# Mouse-112.net
KiCad netlist of a schematic drawn in EAGLE
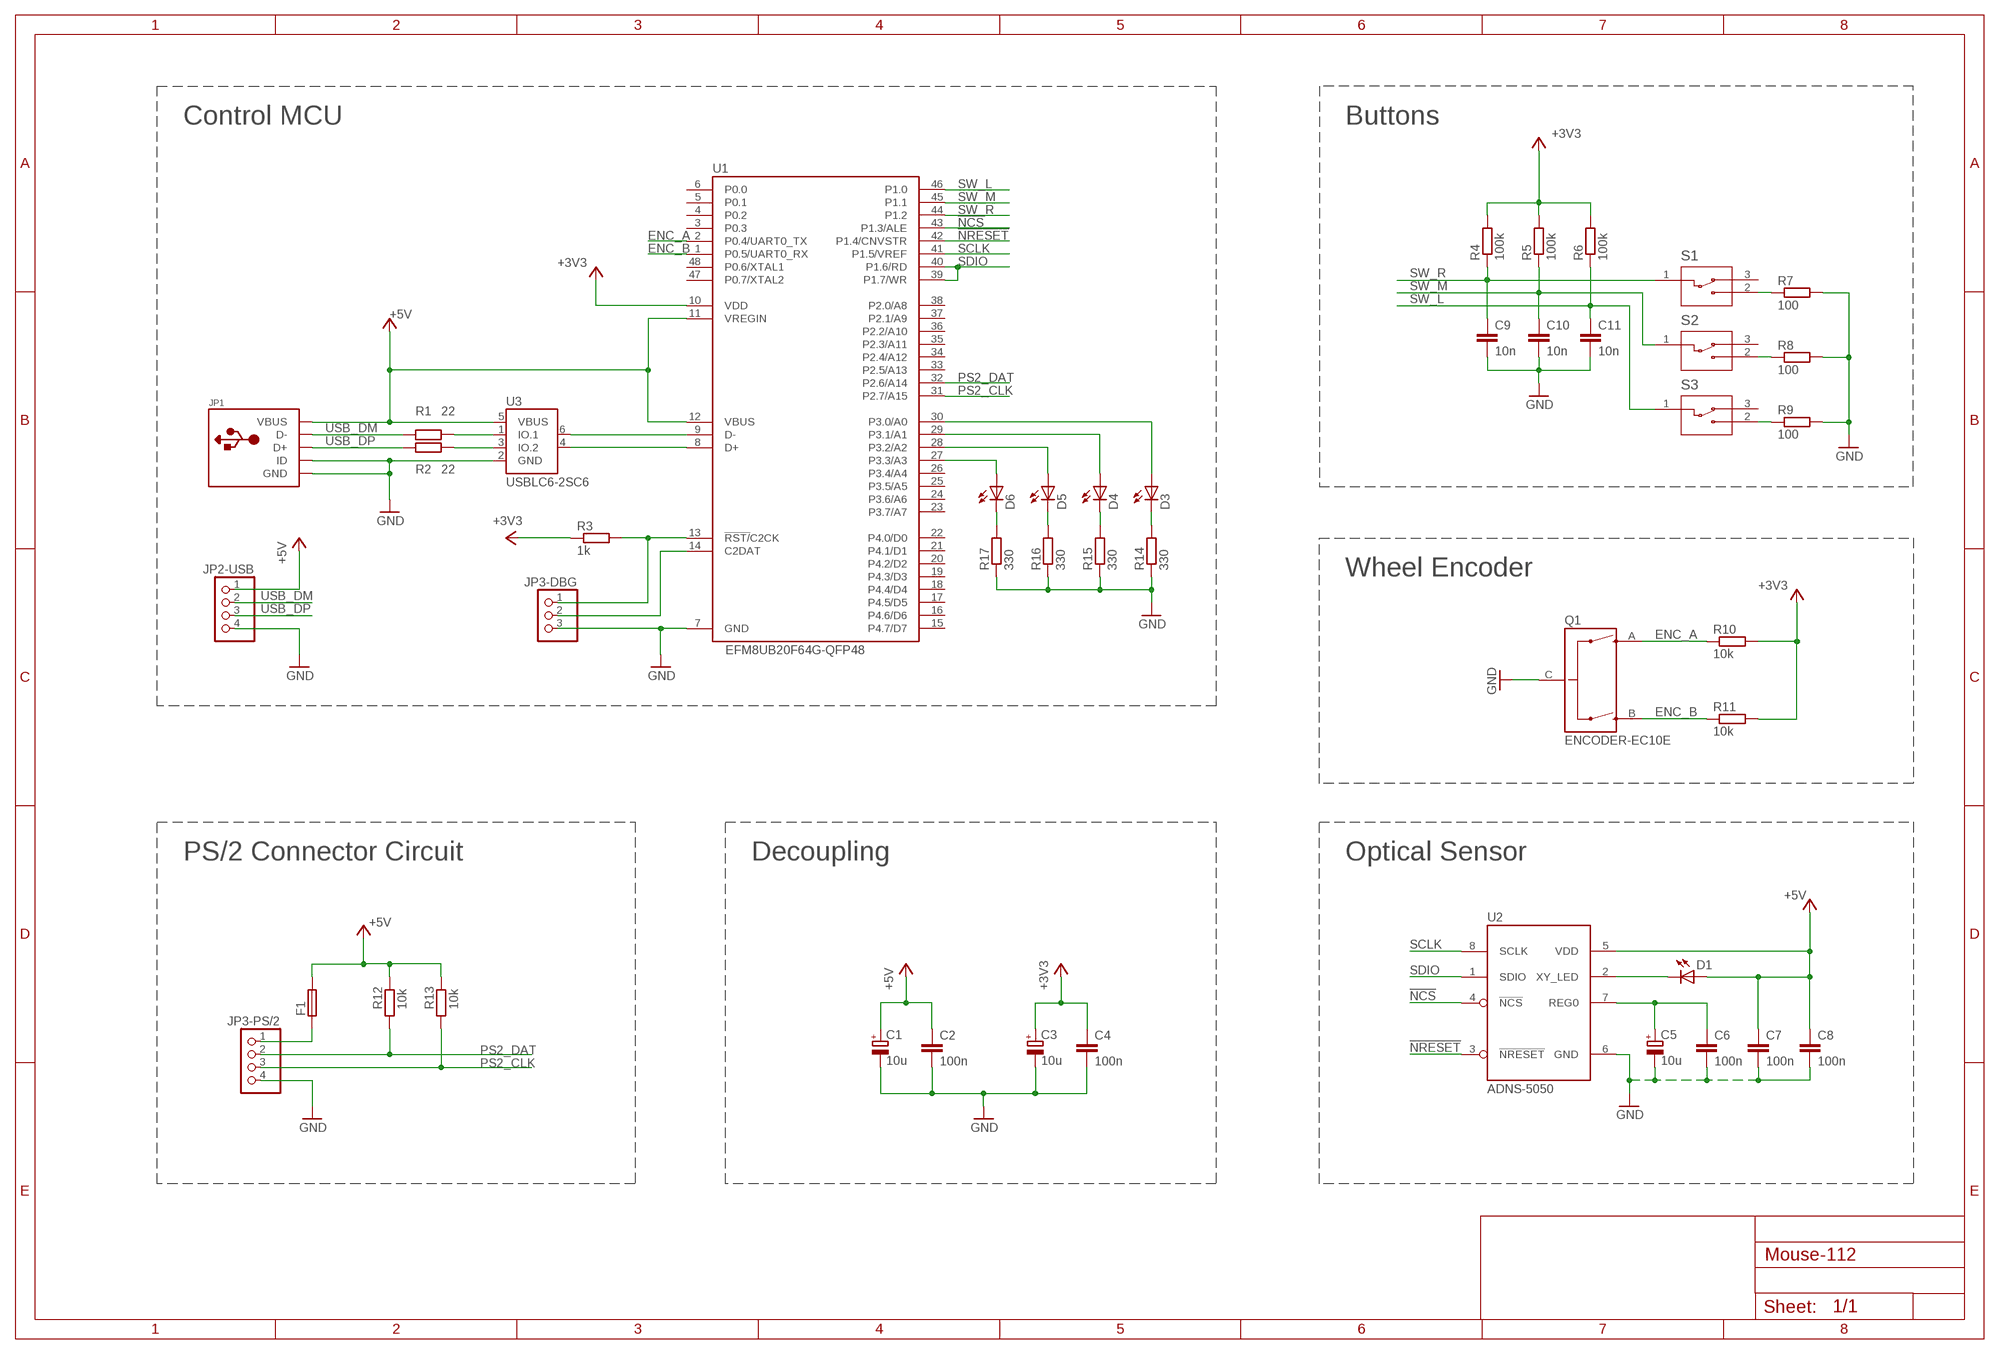
[diagram p0: schematic, sheet 1]

(export (version "E")
  (design (tool "Eeschema 10.0.6"))
  (components
    (comp (ref "C1")
      (value "10u")
      (footprint "eagle-import:RCL-1206F-POL")
      (libsource (lib "eagle-import") (part "CPOL-EU"))
    )
    (comp (ref "C2")
      (value "100n")
      (footprint "eagle-import:RCL-0805F")
      (libsource (lib "eagle-import") (part "C-EU0805"))
    )
    (comp (ref "C3")
      (value "10u")
      (footprint "eagle-import:RCL-1206F-POL")
      (libsource (lib "eagle-import") (part "CPOL-EU"))
    )
    (comp (ref "C4")
      (value "100n")
      (footprint "eagle-import:RCL-0805F")
      (libsource (lib "eagle-import") (part "C-EU0805"))
    )
    (comp (ref "C5")
      (value "10u")
      (footprint "eagle-import:RCL-1206F-POL")
      (libsource (lib "eagle-import") (part "CPOL-EU"))
    )
    (comp (ref "C6")
      (value "100n")
      (footprint "eagle-import:RCL-0805F")
      (libsource (lib "eagle-import") (part "C-EU0805"))
    )
    (comp (ref "C7")
      (value "100n")
      (footprint "eagle-import:RCL-0805F")
      (libsource (lib "eagle-import") (part "C-EU0805"))
    )
    (comp (ref "C8")
      (value "100n")
      (footprint "eagle-import:RCL-0805F")
      (libsource (lib "eagle-import") (part "C-EU0805"))
    )
    (comp (ref "C9")
      (value "10n")
      (footprint "eagle-import:RCL-0805F")
      (libsource (lib "eagle-import") (part "C-EU0805"))
    )
    (comp (ref "C10")
      (value "10n")
      (footprint "eagle-import:RCL-0805F")
      (libsource (lib "eagle-import") (part "C-EU0805"))
    )
    (comp (ref "C11")
      (value "10n")
      (footprint "eagle-import:RCL-0805F")
      (libsource (lib "eagle-import") (part "C-EU0805"))
    )
    (comp (ref "D1")
      (value "LED5MM")
      (footprint "eagle-import:LED5MM")
      (libsource (lib "eagle-import") (part "LED5MM"))
    )
    (comp (ref "D3")
      (value "LEDLED-0805F")
      (footprint "eagle-import:LED-0805F")
      (libsource (lib "eagle-import") (part "LEDLED-0805F"))
    )
    (comp (ref "D4")
      (value "LEDLED-0805F")
      (footprint "eagle-import:LED-0805F")
      (libsource (lib "eagle-import") (part "LEDLED-0805F"))
    )
    (comp (ref "D5")
      (value "LEDLED-0805F")
      (footprint "eagle-import:LED-0805F")
      (libsource (lib "eagle-import") (part "LEDLED-0805F"))
    )
    (comp (ref "D6")
      (value "LEDLED-0805F")
      (footprint "eagle-import:LED-0805F")
      (libsource (lib "eagle-import") (part "LEDLED-0805F"))
    )
    (comp (ref "F1")
      (value "FUSE-NSMF")
      (footprint "eagle-import:RCL-1206F")
      (libsource (lib "eagle-import") (part "FUSE-NSMF"))
    )
    (comp (ref "JP1")
      (value "USB-MINI")
      (footprint "eagle-import:USB-MINIB")
      (libsource (lib "eagle-import") (part "USB-MINI"))
    )
    (comp (ref "JP2-USB")
      (value "PINHD-1X4")
      (footprint "eagle-import:1X04")
      (libsource (lib "eagle-import") (part "PINHD-1X4"))
    )
    (comp (ref "JP3-DBG")
      (value "PINHD-1X3")
      (footprint "eagle-import:1X03")
      (libsource (lib "eagle-import") (part "PINHD-1X3"))
    )
    (comp (ref "JP3-PS/2")
      (value "PINHD-1X4")
      (footprint "eagle-import:1X04")
      (libsource (lib "eagle-import") (part "PINHD-1X4"))
    )
    (comp (ref "Q1")
      (value "ENCODER-EC10E")
      (footprint "eagle-import:ENCODER-10MM")
      (libsource (lib "eagle-import") (part "ENCODER-EC10E"))
    )
    (comp (ref "R1")
      (value "22")
      (footprint "eagle-import:RCL-0805F")
      (libsource (lib "eagle-import") (part "R-EU0805"))
    )
    (comp (ref "R2")
      (value "22")
      (footprint "eagle-import:RCL-0805F")
      (libsource (lib "eagle-import") (part "R-EU0805"))
    )
    (comp (ref "R3")
      (value "1k")
      (footprint "eagle-import:RCL-0805F")
      (libsource (lib "eagle-import") (part "R-EU0805"))
    )
    (comp (ref "R4")
      (value "100k")
      (footprint "eagle-import:RCL-0805F")
      (libsource (lib "eagle-import") (part "R-EU0805"))
    )
    (comp (ref "R5")
      (value "100k")
      (footprint "eagle-import:RCL-0805F")
      (libsource (lib "eagle-import") (part "R-EU0805"))
    )
    (comp (ref "R6")
      (value "100k")
      (footprint "eagle-import:RCL-0805F")
      (libsource (lib "eagle-import") (part "R-EU0805"))
    )
    (comp (ref "R7")
      (value "100")
      (footprint "eagle-import:RCL-0805F")
      (libsource (lib "eagle-import") (part "R-EU0805"))
    )
    (comp (ref "R8")
      (value "100")
      (footprint "eagle-import:RCL-0805F")
      (libsource (lib "eagle-import") (part "R-EU0805"))
    )
    (comp (ref "R9")
      (value "100")
      (footprint "eagle-import:RCL-0805F")
      (libsource (lib "eagle-import") (part "R-EU0805"))
    )
    (comp (ref "R10")
      (value "10k")
      (footprint "eagle-import:RCL-0805F")
      (libsource (lib "eagle-import") (part "R-EU0805"))
    )
    (comp (ref "R11")
      (value "10k")
      (footprint "eagle-import:RCL-0805F")
      (libsource (lib "eagle-import") (part "R-EU0805"))
    )
    (comp (ref "R12")
      (value "10k")
      (footprint "eagle-import:RCL-0805F")
      (libsource (lib "eagle-import") (part "R-EU0805"))
    )
    (comp (ref "R13")
      (value "10k")
      (footprint "eagle-import:RCL-0805F")
      (libsource (lib "eagle-import") (part "R-EU0805"))
    )
    (comp (ref "R14")
      (value "330")
      (footprint "eagle-import:RCL-0805F")
      (libsource (lib "eagle-import") (part "R-EU0805"))
    )
    (comp (ref "R15")
      (value "330")
      (footprint "eagle-import:RCL-0805F")
      (libsource (lib "eagle-import") (part "R-EU0805"))
    )
    (comp (ref "R16")
      (value "330")
      (footprint "eagle-import:RCL-0805F")
      (libsource (lib "eagle-import") (part "R-EU0805"))
    )
    (comp (ref "R17")
      (value "330")
      (footprint "eagle-import:RCL-0805F")
      (libsource (lib "eagle-import") (part "R-EU0805"))
    )
    (comp (ref "S1")
      (value "SWITCH-D2F-01")
      (footprint "eagle-import:SWITCH-D2F-01L-12.8X5.8MM")
      (libsource (lib "eagle-import") (part "SWITCH-D2F-01"))
    )
    (comp (ref "S2")
      (value "SWITCH-D2F-01")
      (footprint "eagle-import:SWITCH-D2F-01L-12.8X5.8MM")
      (libsource (lib "eagle-import") (part "SWITCH-D2F-01"))
    )
    (comp (ref "S3")
      (value "SWITCH-D2F-01")
      (footprint "eagle-import:SWITCH-D2F-01L-12.8X5.8MM")
      (libsource (lib "eagle-import") (part "SWITCH-D2F-01"))
    )
    (comp (ref "U1")
      (value "EFM8UB20F64G-QFP48")
      (footprint "eagle-import:QFP48-7X7-0P5MM")
      (fields (field (name "MFG") "Silicon Laboratories"))
      (libsource (lib "eagle-import") (part "EFM8UB20F64G-QFP48"))
    )
    (comp (ref "U2")
      (value "ADNS-5050")
      (footprint "eagle-import:ADNS-5050-DIP-8")
      (libsource (lib "eagle-import") (part "ADNS-5050"))
    )
    (comp (ref "U3")
      (value "USBLC6-2SC6")
      (footprint "eagle-import:SOT-23-6L")
      (libsource (lib "eagle-import") (part "USBLC6-2SC6"))
    )
  )
  (nets
    (net (code "1") (name "+3V3") (class "Default")
      (node (ref "C3") (pin "+") (pinfunction "+_+") (pintype "passive"))
      (node (ref "C4") (pin "1") (pinfunction "1_1") (pintype "passive"))
      (node (ref "R10") (pin "2") (pinfunction "2_2") (pintype "passive"))
      (node (ref "R11") (pin "2") (pinfunction "2_2") (pintype "passive"))
      (node (ref "R3") (pin "1") (pinfunction "1_1") (pintype "passive"))
      (node (ref "R4") (pin "2") (pinfunction "2_2") (pintype "passive"))
      (node (ref "R5") (pin "2") (pinfunction "2_2") (pintype "passive"))
      (node (ref "R6") (pin "2") (pinfunction "2_2") (pintype "passive"))
      (node (ref "U1") (pin "10") (pinfunction "VDD_10") (pintype "bidirectional"))
    )
    (net (code "2") (name "+5V") (class "Default")
      (node (ref "C1") (pin "+") (pinfunction "+_+") (pintype "passive"))
      (node (ref "C2") (pin "1") (pinfunction "1_1") (pintype "passive"))
      (node (ref "C7") (pin "1") (pinfunction "1_1") (pintype "passive"))
      (node (ref "C8") (pin "1") (pinfunction "1_1") (pintype "passive"))
      (node (ref "D1") (pin "A") (pinfunction "A_A") (pintype "passive"))
      (node (ref "F1") (pin "2") (pinfunction "2_2") (pintype "passive"))
      (node (ref "JP1") (pin "VBUS") (pinfunction "VBUS_VBUS") (pintype "power_in"))
      (node (ref "JP2-USB") (pin "1") (pinfunction "1_1") (pintype "passive"))
      (node (ref "R12") (pin "2") (pinfunction "2_2") (pintype "passive"))
      (node (ref "R13") (pin "2") (pinfunction "2_2") (pintype "passive"))
      (node (ref "U1") (pin "11") (pinfunction "VREGIN_11") (pintype "bidirectional"))
      (node (ref "U1") (pin "12") (pinfunction "VBUS_12") (pintype "bidirectional"))
      (node (ref "U2") (pin "5") (pinfunction "VDD_5") (pintype "power_in"))
      (node (ref "U3") (pin "5") (pinfunction "VBUS_5") (pintype "bidirectional"))
    )
    (net (code "3") (name "/ENC_A") (class "Default")
      (node (ref "Q1") (pin "A") (pinfunction "A_A") (pintype "bidirectional"))
      (node (ref "R10") (pin "1") (pinfunction "1_1") (pintype "passive"))
      (node (ref "U1") (pin "2") (pinfunction "P0.4/UART0_TX_2") (pintype "bidirectional"))
    )
    (net (code "4") (name "/ENC_B") (class "Default")
      (node (ref "Q1") (pin "B") (pinfunction "B_B") (pintype "bidirectional"))
      (node (ref "R11") (pin "1") (pinfunction "1_1") (pintype "passive"))
      (node (ref "U1") (pin "1") (pinfunction "P0.5/UART0_RX_1") (pintype "bidirectional"))
    )
    (net (code "5") (name "/PS2_CLK") (class "Default")
      (node (ref "JP3-PS/2") (pin "3") (pinfunction "3_3") (pintype "passive"))
      (node (ref "R13") (pin "1") (pinfunction "1_1") (pintype "passive"))
      (node (ref "U1") (pin "31") (pinfunction "P2.7/A15_31") (pintype "bidirectional"))
    )
    (net (code "6") (name "/PS2_DAT") (class "Default")
      (node (ref "JP3-PS/2") (pin "2") (pinfunction "2_2") (pintype "passive"))
      (node (ref "R12") (pin "1") (pinfunction "1_1") (pintype "passive"))
      (node (ref "U1") (pin "32") (pinfunction "P2.6/A14_32") (pintype "bidirectional"))
    )
    (net (code "7") (name "/SCLK") (class "Default")
      (node (ref "U1") (pin "41") (pinfunction "P1.5/VREF_41") (pintype "bidirectional"))
      (node (ref "U2") (pin "8") (pinfunction "SCLK_8") (pintype "bidirectional"))
    )
    (net (code "8") (name "/SDIO") (class "Default")
      (node (ref "U1") (pin "39") (pinfunction "P1.7/WR_39") (pintype "bidirectional"))
      (node (ref "U1") (pin "40") (pinfunction "P1.6/RD_40") (pintype "bidirectional"))
      (node (ref "U2") (pin "1") (pinfunction "SDIO_1") (pintype "bidirectional"))
    )
    (net (code "9") (name "/SW_L") (class "Default")
      (node (ref "C11") (pin "1") (pinfunction "1_1") (pintype "passive"))
      (node (ref "R6") (pin "1") (pinfunction "1_1") (pintype "passive"))
      (node (ref "S3") (pin "1") (pinfunction "1_1") (pintype "passive"))
      (node (ref "U1") (pin "46") (pinfunction "P1.0_46") (pintype "bidirectional"))
    )
    (net (code "10") (name "/SW_M") (class "Default")
      (node (ref "C10") (pin "1") (pinfunction "1_1") (pintype "passive"))
      (node (ref "R5") (pin "1") (pinfunction "1_1") (pintype "passive"))
      (node (ref "S2") (pin "1") (pinfunction "1_1") (pintype "passive"))
      (node (ref "U1") (pin "45") (pinfunction "P1.1_45") (pintype "bidirectional"))
    )
    (net (code "11") (name "/SW_R") (class "Default")
      (node (ref "C9") (pin "1") (pinfunction "1_1") (pintype "passive"))
      (node (ref "R4") (pin "1") (pinfunction "1_1") (pintype "passive"))
      (node (ref "S1") (pin "1") (pinfunction "1_1") (pintype "passive"))
      (node (ref "U1") (pin "44") (pinfunction "P1.2_44") (pintype "bidirectional"))
    )
    (net (code "12") (name "/USB_DM") (class "Default")
      (node (ref "JP1") (pin "D-") (pinfunction "D-_D-") (pintype "bidirectional"))
      (node (ref "JP2-USB") (pin "2") (pinfunction "2_2") (pintype "passive"))
      (node (ref "R1") (pin "1") (pinfunction "1_1") (pintype "passive"))
    )
    (net (code "13") (name "/USB_DP") (class "Default")
      (node (ref "JP1") (pin "D+") (pinfunction "D+_D+") (pintype "bidirectional"))
      (node (ref "JP2-USB") (pin "3") (pinfunction "3_3") (pintype "passive"))
      (node (ref "R2") (pin "1") (pinfunction "1_1") (pintype "passive"))
    )
    (net (code "14") (name "/~{NCS}") (class "Default")
      (node (ref "U1") (pin "43") (pinfunction "P1.3/ALE_43") (pintype "bidirectional"))
      (node (ref "U2") (pin "4") (pinfunction "~{NCS}_4") (pintype "bidirectional"))
    )
    (net (code "15") (name "/~{NRESET}") (class "Default")
      (node (ref "U1") (pin "42") (pinfunction "P1.4/CNVSTR_42") (pintype "bidirectional"))
      (node (ref "U2") (pin "3") (pinfunction "~{NRESET}_3") (pintype "bidirectional"))
    )
    (net (code "16") (name "GND") (class "Default")
      (node (ref "C1") (pin "-") (pinfunction "-_-") (pintype "passive"))
      (node (ref "C10") (pin "2") (pinfunction "2_2") (pintype "passive"))
      (node (ref "C11") (pin "2") (pinfunction "2_2") (pintype "passive"))
      (node (ref "C2") (pin "2") (pinfunction "2_2") (pintype "passive"))
      (node (ref "C3") (pin "-") (pinfunction "-_-") (pintype "passive"))
      (node (ref "C4") (pin "2") (pinfunction "2_2") (pintype "passive"))
      (node (ref "C5") (pin "-") (pinfunction "-_-") (pintype "passive"))
      (node (ref "C6") (pin "2") (pinfunction "2_2") (pintype "passive"))
      (node (ref "C7") (pin "2") (pinfunction "2_2") (pintype "passive"))
      (node (ref "C8") (pin "2") (pinfunction "2_2") (pintype "passive"))
      (node (ref "C9") (pin "2") (pinfunction "2_2") (pintype "passive"))
      (node (ref "JP1") (pin "GND") (pinfunction "GND_GND") (pintype "power_in"))
      (node (ref "JP1") (pin "ID") (pinfunction "ID_ID") (pintype "bidirectional"))
      (node (ref "JP2-USB") (pin "4") (pinfunction "4_4") (pintype "passive"))
      (node (ref "JP3-DBG") (pin "3") (pinfunction "3_3") (pintype "passive"))
      (node (ref "JP3-PS/2") (pin "4") (pinfunction "4_4") (pintype "passive"))
      (node (ref "Q1") (pin "C") (pinfunction "C_C") (pintype "bidirectional"))
      (node (ref "R14") (pin "1") (pinfunction "1_1") (pintype "passive"))
      (node (ref "R15") (pin "1") (pinfunction "1_1") (pintype "passive"))
      (node (ref "R16") (pin "1") (pinfunction "1_1") (pintype "passive"))
      (node (ref "R17") (pin "1") (pinfunction "1_1") (pintype "passive"))
      (node (ref "R7") (pin "2") (pinfunction "2_2") (pintype "passive"))
      (node (ref "R8") (pin "2") (pinfunction "2_2") (pintype "passive"))
      (node (ref "R9") (pin "2") (pinfunction "2_2") (pintype "passive"))
      (node (ref "U1") (pin "7") (pinfunction "GND_7") (pintype "bidirectional"))
      (node (ref "U2") (pin "6") (pinfunction "GND_6") (pintype "power_in"))
      (node (ref "U3") (pin "2") (pinfunction "GND_2") (pintype "power_in"))
    )
    (net (code "17") (name "Net-(D1-C)") (class "Default")
      (node (ref "D1") (pin "K") (pinfunction "C_K") (pintype "passive"))
      (node (ref "U2") (pin "2") (pinfunction "XY_LED_2") (pintype "bidirectional"))
    )
    (net (code "18") (name "Net-(D3-PadC)") (class "Default")
      (node (ref "D3") (pin "C") (pinfunction "C_C") (pintype "passive"))
      (node (ref "R14") (pin "2") (pinfunction "2_2") (pintype "passive"))
    )
    (net (code "19") (name "Net-(D4-PadC)") (class "Default")
      (node (ref "D4") (pin "C") (pinfunction "C_C") (pintype "passive"))
      (node (ref "R15") (pin "2") (pinfunction "2_2") (pintype "passive"))
    )
    (net (code "20") (name "Net-(D5-PadC)") (class "Default")
      (node (ref "D5") (pin "C") (pinfunction "C_C") (pintype "passive"))
      (node (ref "R16") (pin "2") (pinfunction "2_2") (pintype "passive"))
    )
    (net (code "21") (name "Net-(D6-PadC)") (class "Default")
      (node (ref "D6") (pin "C") (pinfunction "C_C") (pintype "passive"))
      (node (ref "R17") (pin "2") (pinfunction "2_2") (pintype "passive"))
    )
    (net (code "22") (name "Net-(F1-Pad1)") (class "Default")
      (node (ref "F1") (pin "1") (pinfunction "1_1") (pintype "passive"))
      (node (ref "JP3-PS/2") (pin "1") (pinfunction "1_1") (pintype "passive"))
    )
    (net (code "23") (name "Net-(R7-Pad1)") (class "Default")
      (node (ref "R7") (pin "1") (pinfunction "1_1") (pintype "passive"))
      (node (ref "S1") (pin "2") (pinfunction "2_2") (pintype "passive"))
    )
    (net (code "24") (name "Net-(R8-Pad1)") (class "Default")
      (node (ref "R8") (pin "1") (pinfunction "1_1") (pintype "passive"))
      (node (ref "S2") (pin "2") (pinfunction "2_2") (pintype "passive"))
    )
    (net (code "25") (name "Net-(R9-Pad1)") (class "Default")
      (node (ref "R9") (pin "1") (pinfunction "1_1") (pintype "passive"))
      (node (ref "S3") (pin "2") (pinfunction "2_2") (pintype "passive"))
    )
    (net (code "26") (name "Net-(U1-C2DAT)") (class "Default")
      (node (ref "JP3-DBG") (pin "2") (pinfunction "2_2") (pintype "passive"))
      (node (ref "U1") (pin "14") (pinfunction "C2DAT_14") (pintype "bidirectional"))
    )
    (net (code "27") (name "Net-(U1-D+)") (class "Default")
      (node (ref "U1") (pin "8") (pinfunction "D+_8") (pintype "bidirectional"))
      (node (ref "U3") (pin "4") (pinfunction "IO_2_4") (pintype "bidirectional"))
    )
    (net (code "28") (name "Net-(U1-D-)") (class "Default")
      (node (ref "U1") (pin "9") (pinfunction "D-_9") (pintype "bidirectional"))
      (node (ref "U3") (pin "6") (pinfunction "IO_1_6") (pintype "bidirectional"))
    )
    (net (code "29") (name "Net-(U1-P3.0{slash}A0)") (class "Default")
      (node (ref "D3") (pin "A") (pinfunction "A_A") (pintype "passive"))
      (node (ref "U1") (pin "30") (pinfunction "P3.0/A0_30") (pintype "bidirectional"))
    )
    (net (code "30") (name "Net-(U1-P3.1{slash}A1)") (class "Default")
      (node (ref "D4") (pin "A") (pinfunction "A_A") (pintype "passive"))
      (node (ref "U1") (pin "29") (pinfunction "P3.1/A1_29") (pintype "bidirectional"))
    )
    (net (code "31") (name "Net-(U1-P3.2{slash}A2)") (class "Default")
      (node (ref "D5") (pin "A") (pinfunction "A_A") (pintype "passive"))
      (node (ref "U1") (pin "28") (pinfunction "P3.2/A2_28") (pintype "bidirectional"))
    )
    (net (code "32") (name "Net-(U1-P3.3{slash}A3)") (class "Default")
      (node (ref "D6") (pin "A") (pinfunction "A_A") (pintype "passive"))
      (node (ref "U1") (pin "27") (pinfunction "P3.3/A3_27") (pintype "bidirectional"))
    )
    (net (code "33") (name "Net-(U1-~{RST{slash}}C2CK)") (class "Default")
      (node (ref "JP3-DBG") (pin "1") (pinfunction "1_1") (pintype "passive"))
      (node (ref "R3") (pin "2") (pinfunction "2_2") (pintype "passive"))
      (node (ref "U1") (pin "13") (pinfunction "~{RST/}C2CK_13") (pintype "bidirectional"))
    )
    (net (code "34") (name "Net-(U2-REG0)") (class "Default")
      (node (ref "C5") (pin "+") (pinfunction "+_+") (pintype "passive"))
      (node (ref "C6") (pin "1") (pinfunction "1_1") (pintype "passive"))
      (node (ref "U2") (pin "7") (pinfunction "REG0_7") (pintype "bidirectional"))
    )
    (net (code "35") (name "Net-(U3-IO.1)") (class "Default")
      (node (ref "R1") (pin "2") (pinfunction "2_2") (pintype "passive"))
      (node (ref "U3") (pin "1") (pinfunction "IO.1_1") (pintype "bidirectional"))
    )
    (net (code "36") (name "Net-(U3-IO.2)") (class "Default")
      (node (ref "R2") (pin "2") (pinfunction "2_2") (pintype "passive"))
      (node (ref "U3") (pin "3") (pinfunction "IO.2_3") (pintype "bidirectional"))
    )
    (net (code "37") (name "unconnected-(S1-Pad3)") (class "Default")
      (node (ref "S1") (pin "3") (pinfunction "3_3") (pintype "passive"))
    )
    (net (code "38") (name "unconnected-(S2-Pad3)") (class "Default")
      (node (ref "S2") (pin "3") (pinfunction "3_3") (pintype "passive"))
    )
    (net (code "39") (name "unconnected-(S3-Pad3)") (class "Default")
      (node (ref "S3") (pin "3") (pinfunction "3_3") (pintype "passive"))
    )
    (net (code "40") (name "unconnected-(U1-P0.0-Pad6)") (class "Default")
      (node (ref "U1") (pin "6") (pinfunction "P0.0_6") (pintype "bidirectional"))
    )
    (net (code "41") (name "unconnected-(U1-P0.1-Pad5)") (class "Default")
      (node (ref "U1") (pin "5") (pinfunction "P0.1_5") (pintype "bidirectional"))
    )
    (net (code "42") (name "unconnected-(U1-P0.2-Pad4)") (class "Default")
      (node (ref "U1") (pin "4") (pinfunction "P0.2_4") (pintype "bidirectional"))
    )
    (net (code "43") (name "unconnected-(U1-P0.3-Pad3)") (class "Default")
      (node (ref "U1") (pin "3") (pinfunction "P0.3_3") (pintype "bidirectional"))
    )
    (net (code "44") (name "unconnected-(U1-P0.6{slash}XTAL1-Pad48)") (class "Default")
      (node (ref "U1") (pin "48") (pinfunction "P0.6/XTAL1_48") (pintype "bidirectional"))
    )
    (net (code "45") (name "unconnected-(U1-P0.7{slash}XTAL2-Pad47)") (class "Default")
      (node (ref "U1") (pin "47") (pinfunction "P0.7/XTAL2_47") (pintype "bidirectional"))
    )
    (net (code "46") (name "unconnected-(U1-P2.0{slash}A8-Pad38)") (class "Default")
      (node (ref "U1") (pin "38") (pinfunction "P2.0/A8_38") (pintype "bidirectional"))
    )
    (net (code "47") (name "unconnected-(U1-P2.1{slash}A9-Pad37)") (class "Default")
      (node (ref "U1") (pin "37") (pinfunction "P2.1/A9_37") (pintype "bidirectional"))
    )
    (net (code "48") (name "unconnected-(U1-P2.2{slash}A10-Pad36)") (class "Default")
      (node (ref "U1") (pin "36") (pinfunction "P2.2/A10_36") (pintype "bidirectional"))
    )
    (net (code "49") (name "unconnected-(U1-P2.3{slash}A11-Pad35)") (class "Default")
      (node (ref "U1") (pin "35") (pinfunction "P2.3/A11_35") (pintype "bidirectional"))
    )
    (net (code "50") (name "unconnected-(U1-P2.4{slash}A12-Pad34)") (class "Default")
      (node (ref "U1") (pin "34") (pinfunction "P2.4/A12_34") (pintype "bidirectional"))
    )
    (net (code "51") (name "unconnected-(U1-P2.5{slash}A13-Pad33)") (class "Default")
      (node (ref "U1") (pin "33") (pinfunction "P2.5/A13_33") (pintype "bidirectional"))
    )
    (net (code "52") (name "unconnected-(U1-P3.4{slash}A4-Pad26)") (class "Default")
      (node (ref "U1") (pin "26") (pinfunction "P3.4/A4_26") (pintype "bidirectional"))
    )
    (net (code "53") (name "unconnected-(U1-P3.5{slash}A5-Pad25)") (class "Default")
      (node (ref "U1") (pin "25") (pinfunction "P3.5/A5_25") (pintype "bidirectional"))
    )
    (net (code "54") (name "unconnected-(U1-P3.6{slash}A6-Pad24)") (class "Default")
      (node (ref "U1") (pin "24") (pinfunction "P3.6/A6_24") (pintype "bidirectional"))
    )
    (net (code "55") (name "unconnected-(U1-P3.7{slash}A7-Pad23)") (class "Default")
      (node (ref "U1") (pin "23") (pinfunction "P3.7/A7_23") (pintype "bidirectional"))
    )
    (net (code "56") (name "unconnected-(U1-P4.0{slash}D0-Pad22)") (class "Default")
      (node (ref "U1") (pin "22") (pinfunction "P4.0/D0_22") (pintype "bidirectional"))
    )
    (net (code "57") (name "unconnected-(U1-P4.1{slash}D1-Pad21)") (class "Default")
      (node (ref "U1") (pin "21") (pinfunction "P4.1/D1_21") (pintype "bidirectional"))
    )
    (net (code "58") (name "unconnected-(U1-P4.2{slash}D2-Pad20)") (class "Default")
      (node (ref "U1") (pin "20") (pinfunction "P4.2/D2_20") (pintype "bidirectional"))
    )
    (net (code "59") (name "unconnected-(U1-P4.3{slash}D3-Pad19)") (class "Default")
      (node (ref "U1") (pin "19") (pinfunction "P4.3/D3_19") (pintype "bidirectional"))
    )
    (net (code "60") (name "unconnected-(U1-P4.4{slash}D4-Pad18)") (class "Default")
      (node (ref "U1") (pin "18") (pinfunction "P4.4/D4_18") (pintype "bidirectional"))
    )
    (net (code "61") (name "unconnected-(U1-P4.5{slash}D5-Pad17)") (class "Default")
      (node (ref "U1") (pin "17") (pinfunction "P4.5/D5_17") (pintype "bidirectional"))
    )
    (net (code "62") (name "unconnected-(U1-P4.6{slash}D6-Pad16)") (class "Default")
      (node (ref "U1") (pin "16") (pinfunction "P4.6/D6_16") (pintype "bidirectional"))
    )
    (net (code "63") (name "unconnected-(U1-P4.7{slash}D7-Pad15)") (class "Default")
      (node (ref "U1") (pin "15") (pinfunction "P4.7/D7_15") (pintype "bidirectional"))
    )
  )
)
